# OhEye.net
KiCad netlist of a schematic drawn in EAGLE
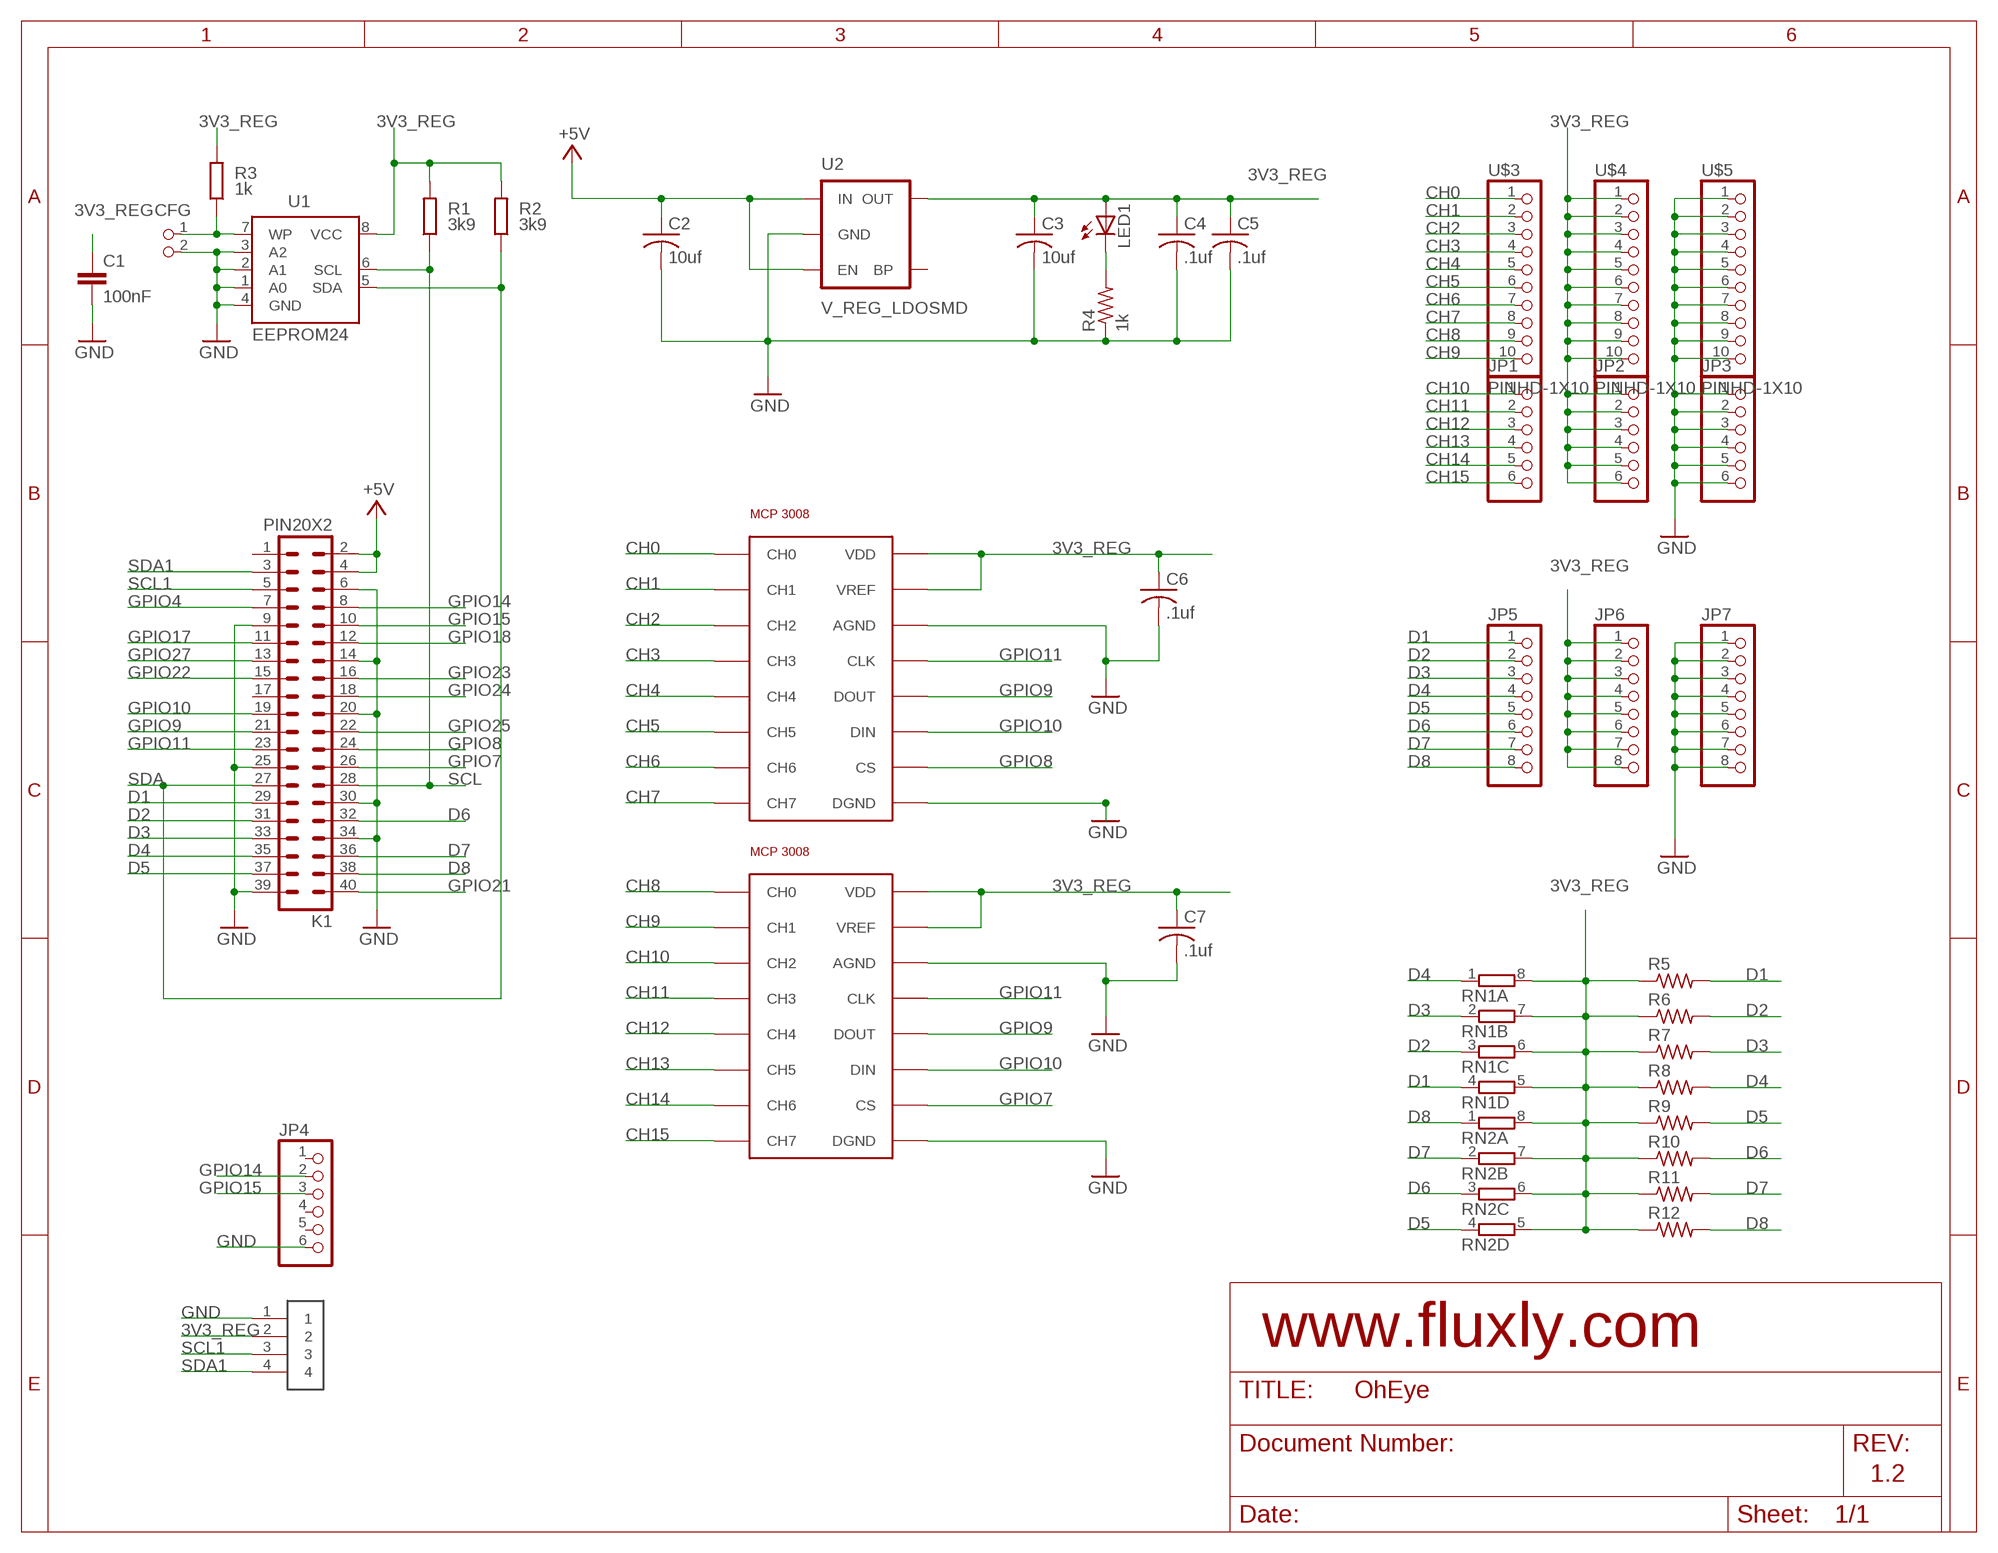
[diagram p0: schematic, sheet 1]

(export (version "E")
  (design (tool "Eeschema 10.0.6"))
  (components
    (comp (ref "C1")
      (value "100nF")
      (footprint "eagle-import:C0805K")
      (libsource (lib "eagle-import") (part "C-EUC0805K"))
    )
    (comp (ref "C2")
      (value "10uf")
      (footprint "eagle-import:C0805K")
      (libsource (lib "eagle-import") (part "C-USC0805K"))
    )
    (comp (ref "C3")
      (value "10uf")
      (footprint "eagle-import:C0805K")
      (libsource (lib "eagle-import") (part "C-USC0805K"))
    )
    (comp (ref "C4")
      (value ".1uf")
      (footprint "eagle-import:C0805K")
      (libsource (lib "eagle-import") (part "C-USC0805K"))
    )
    (comp (ref "C5")
      (value ".1uf")
      (footprint "eagle-import:C0805K")
      (libsource (lib "eagle-import") (part "C-USC0805K"))
    )
    (comp (ref "C6")
      (value ".1uf")
      (footprint "eagle-import:C0805K")
      (libsource (lib "eagle-import") (part "C-USC0805K"))
    )
    (comp (ref "C7")
      (value ".1uf")
      (footprint "eagle-import:C0805K")
      (libsource (lib "eagle-import") (part "C-USC0805K"))
    )
    (comp (ref "CFG")
      (value "PIN2_100")
      (footprint "eagle-import:PIN_W_2")
      (libsource (lib "eagle-import") (part "PIN2_100"))
    )
    (comp (ref "JP1")
      (value "PINHD-1X6B")
      (footprint "eagle-import:1X06-BIG")
      (libsource (lib "eagle-import") (part "PINHD-1X6B"))
    )
    (comp (ref "JP2")
      (value "PINHD-1X6B")
      (footprint "eagle-import:1X06-BIG")
      (libsource (lib "eagle-import") (part "PINHD-1X6B"))
    )
    (comp (ref "JP3")
      (value "PINHD-1X6B")
      (footprint "eagle-import:1X06-BIG")
      (libsource (lib "eagle-import") (part "PINHD-1X6B"))
    )
    (comp (ref "JP4")
      (value "PINHD-1X6B")
      (footprint "eagle-import:1X06-BIG")
      (libsource (lib "eagle-import") (part "PINHD-1X6B"))
    )
    (comp (ref "JP5")
      (value "PINHD-1X8BIG")
      (footprint "eagle-import:1X08-BIG")
      (libsource (lib "eagle-import") (part "PINHD-1X8BIG"))
    )
    (comp (ref "JP6")
      (value "PINHD-1X8BIG")
      (footprint "eagle-import:1X08-BIG")
      (libsource (lib "eagle-import") (part "PINHD-1X8BIG"))
    )
    (comp (ref "JP7")
      (value "PINHD-1X8BIG")
      (footprint "eagle-import:1X08-BIG")
      (libsource (lib "eagle-import") (part "PINHD-1X8BIG"))
    )
    (comp (ref "K1")
      (value "PIN20X2")
      (footprint "eagle-import:PIN_20X2")
      (libsource (lib "eagle-import") (part "PIN20X2"))
    )
    (comp (ref "LED1")
      (value "LEDLED-0805")
      (footprint "eagle-import:LED0805.PAC")
      (libsource (lib "eagle-import") (part "LEDLED-0805"))
    )
    (comp (ref "R1")
      (value "3k9")
      (footprint "eagle-import:M0805")
      (fields (field (name "TOLERANCE") "5%"))
      (libsource (lib "eagle-import") (part "R-EU_M0805"))
    )
    (comp (ref "R2")
      (value "3k9")
      (footprint "eagle-import:M0805")
      (fields (field (name "TOLERANCE") "5%"))
      (libsource (lib "eagle-import") (part "R-EU_M0805"))
    )
    (comp (ref "R3")
      (value "1k")
      (footprint "eagle-import:M0805")
      (fields (field (name "TOLERANCE") "5%"))
      (libsource (lib "eagle-import") (part "R-EU_M0805"))
    )
    (comp (ref "R4")
      (value "1k")
      (footprint "eagle-import:R0805W")
      (libsource (lib "eagle-import") (part "R-US_R0805W"))
    )
    (comp (ref "R5")
      (value "R-US_0207/10")
      (footprint "eagle-import:0207_10")
      (libsource (lib "eagle-import") (part "adafruit_R-US_0207/10"))
    )
    (comp (ref "R6")
      (value "R-US_0207/10")
      (footprint "eagle-import:0207_10")
      (libsource (lib "eagle-import") (part "adafruit_R-US_0207/10"))
    )
    (comp (ref "R7")
      (value "R-US_0207/10")
      (footprint "eagle-import:0207_10")
      (libsource (lib "eagle-import") (part "adafruit_R-US_0207/10"))
    )
    (comp (ref "R8")
      (value "R-US_0207/10")
      (footprint "eagle-import:0207_10")
      (libsource (lib "eagle-import") (part "adafruit_R-US_0207/10"))
    )
    (comp (ref "R9")
      (value "R-US_0207/10")
      (footprint "eagle-import:0207_10")
      (libsource (lib "eagle-import") (part "adafruit_R-US_0207/10"))
    )
    (comp (ref "R10")
      (value "R-US_0207/10")
      (footprint "eagle-import:0207_10")
      (libsource (lib "eagle-import") (part "adafruit_R-US_0207/10"))
    )
    (comp (ref "R11")
      (value "R-US_0207/10")
      (footprint "eagle-import:0207_10")
      (libsource (lib "eagle-import") (part "adafruit_R-US_0207/10"))
    )
    (comp (ref "R12")
      (value "R-US_0207/10")
      (footprint "eagle-import:0207_10")
      (libsource (lib "eagle-import") (part "adafruit_R-US_0207/10"))
    )
    (comp (ref "RN1")
      (value "REISTOR_4NETEXBS8V")
      (footprint "eagle-import:EXBS8V")
      (libsource (lib "eagle-import") (part "REISTOR_4NETEXBS8V"))
    )
    (comp (ref "RN2")
      (value "REISTOR_4NETEXBS8V")
      (footprint "eagle-import:EXBS8V")
      (libsource (lib "eagle-import") (part "REISTOR_4NETEXBS8V"))
    )
    (comp (ref "U$1")
      (value "MCP3008_ADC")
      (footprint "eagle-import:SOIC16")
      (libsource (lib "eagle-import") (part "MCP3008_ADC"))
    )
    (comp (ref "U$2")
      (value "MCP3008_ADC")
      (footprint "eagle-import:SOIC16")
      (libsource (lib "eagle-import") (part "MCP3008_ADC"))
    )
    (comp (ref "U$3")
      (value "PINHD-1X10")
      (footprint "eagle-import:1X10-BIG")
      (libsource (lib "eagle-import") (part "PINHD-1X10"))
    )
    (comp (ref "U$4")
      (value "PINHD-1X10")
      (footprint "eagle-import:1X10-BIG")
      (libsource (lib "eagle-import") (part "PINHD-1X10"))
    )
    (comp (ref "U$5")
      (value "PINHD-1X10")
      (footprint "eagle-import:1X10-BIG")
      (libsource (lib "eagle-import") (part "PINHD-1X10"))
    )
    (comp (ref "U$9")
      (value "1X4_CLEAN")
      (footprint "eagle-import:1X4_CLEAN")
      (libsource (lib "eagle-import") (part "1X4_CLEAN"))
    )
    (comp (ref "U1")
      (value "EEPROM24")
      (footprint "eagle-import:SOIC8")
      (libsource (lib "eagle-import") (part "EEPROM24"))
    )
    (comp (ref "U2")
      (value "V_REG_LDOSMD")
      (footprint "eagle-import:SOT23-5")
      (libsource (lib "eagle-import") (part "V_REG_LDOSMD"))
    )
  )
  (nets
    (net (code "1") (name "+5V") (class "Default")
      (node (ref "C2") (pin "1") (pinfunction "1_1") (pintype "passive"))
      (node (ref "K1") (pin "2") (pinfunction "2_2") (pintype "passive"))
      (node (ref "K1") (pin "4") (pinfunction "4_4") (pintype "passive"))
      (node (ref "U2") (pin "1") (pinfunction "IN_1") (pintype "input"))
      (node (ref "U2") (pin "3") (pinfunction "EN_3") (pintype "input"))
    )
    (net (code "2") (name "/3V3_REG") (class "Default")
      (node (ref "C1") (pin "1") (pinfunction "1_1") (pintype "passive"))
      (node (ref "C3") (pin "1") (pinfunction "1_1") (pintype "passive"))
      (node (ref "C4") (pin "1") (pinfunction "1_1") (pintype "passive"))
      (node (ref "C5") (pin "1") (pinfunction "1_1") (pintype "passive"))
      (node (ref "C6") (pin "1") (pinfunction "1_1") (pintype "passive"))
      (node (ref "C7") (pin "1") (pinfunction "1_1") (pintype "passive"))
      (node (ref "JP2") (pin "1") (pinfunction "1_1") (pintype "passive"))
      (node (ref "JP2") (pin "2") (pinfunction "2_2") (pintype "passive"))
      (node (ref "JP2") (pin "3") (pinfunction "3_3") (pintype "passive"))
      (node (ref "JP2") (pin "4") (pinfunction "4_4") (pintype "passive"))
      (node (ref "JP2") (pin "5") (pinfunction "5_5") (pintype "passive"))
      (node (ref "JP2") (pin "6") (pinfunction "6_6") (pintype "passive"))
      (node (ref "JP6") (pin "1") (pinfunction "1_1") (pintype "passive"))
      (node (ref "JP6") (pin "2") (pinfunction "2_2") (pintype "passive"))
      (node (ref "JP6") (pin "3") (pinfunction "3_3") (pintype "passive"))
      (node (ref "JP6") (pin "4") (pinfunction "4_4") (pintype "passive"))
      (node (ref "JP6") (pin "5") (pinfunction "5_5") (pintype "passive"))
      (node (ref "JP6") (pin "6") (pinfunction "6_6") (pintype "passive"))
      (node (ref "JP6") (pin "7") (pinfunction "7_7") (pintype "passive"))
      (node (ref "JP6") (pin "8") (pinfunction "8_8") (pintype "passive"))
      (node (ref "LED1") (pin "A") (pinfunction "A_A") (pintype "passive"))
      (node (ref "R1") (pin "2") (pinfunction "2_2") (pintype "passive"))
      (node (ref "R10") (pin "1") (pinfunction "1_1") (pintype "passive"))
      (node (ref "R11") (pin "1") (pinfunction "1_1") (pintype "passive"))
      (node (ref "R12") (pin "1") (pinfunction "1_1") (pintype "passive"))
      (node (ref "R2") (pin "2") (pinfunction "2_2") (pintype "passive"))
      (node (ref "R3") (pin "2") (pinfunction "2_2") (pintype "passive"))
      (node (ref "R5") (pin "1") (pinfunction "1_1") (pintype "passive"))
      (node (ref "R6") (pin "1") (pinfunction "1_1") (pintype "passive"))
      (node (ref "R7") (pin "1") (pinfunction "1_1") (pintype "passive"))
      (node (ref "R8") (pin "1") (pinfunction "1_1") (pintype "passive"))
      (node (ref "R9") (pin "1") (pinfunction "1_1") (pintype "passive"))
      (node (ref "RN1") (pin "5") (pinfunction "2_5") (pintype "passive"))
      (node (ref "RN1") (pin "6") (pinfunction "2_6") (pintype "passive"))
      (node (ref "RN1") (pin "7") (pinfunction "2_7") (pintype "passive"))
      (node (ref "RN1") (pin "8") (pinfunction "2_8") (pintype "passive"))
      (node (ref "RN2") (pin "5") (pinfunction "2_5") (pintype "passive"))
      (node (ref "RN2") (pin "6") (pinfunction "2_6") (pintype "passive"))
      (node (ref "RN2") (pin "7") (pinfunction "2_7") (pintype "passive"))
      (node (ref "RN2") (pin "8") (pinfunction "2_8") (pintype "passive"))
      (node (ref "U$1") (pin "P$15") (pinfunction "VREF_P$15") (pintype "bidirectional"))
      (node (ref "U$1") (pin "P$16") (pinfunction "VDD_P$16") (pintype "bidirectional"))
      (node (ref "U$2") (pin "P$15") (pinfunction "VREF_P$15") (pintype "bidirectional"))
      (node (ref "U$2") (pin "P$16") (pinfunction "VDD_P$16") (pintype "bidirectional"))
      (node (ref "U$4") (pin "1") (pinfunction "1_1") (pintype "passive"))
      (node (ref "U$4") (pin "10") (pinfunction "10_10") (pintype "passive"))
      (node (ref "U$4") (pin "2") (pinfunction "2_2") (pintype "passive"))
      (node (ref "U$4") (pin "3") (pinfunction "3_3") (pintype "passive"))
      (node (ref "U$4") (pin "4") (pinfunction "4_4") (pintype "passive"))
      (node (ref "U$4") (pin "5") (pinfunction "5_5") (pintype "passive"))
      (node (ref "U$4") (pin "6") (pinfunction "6_6") (pintype "passive"))
      (node (ref "U$4") (pin "7") (pinfunction "7_7") (pintype "passive"))
      (node (ref "U$4") (pin "8") (pinfunction "8_8") (pintype "passive"))
      (node (ref "U$4") (pin "9") (pinfunction "9_9") (pintype "passive"))
      (node (ref "U$9") (pin "2") (pinfunction "2_2") (pintype "bidirectional"))
      (node (ref "U1") (pin "8") (pinfunction "VCC_8") (pintype "power_in"))
      (node (ref "U2") (pin "5") (pinfunction "OUT_5") (pintype "passive"))
    )
    (net (code "3") (name "/CH0") (class "Default")
      (node (ref "U$1") (pin "P$1") (pinfunction "CH0_P$1") (pintype "bidirectional"))
      (node (ref "U$3") (pin "1") (pinfunction "1_1") (pintype "passive"))
    )
    (net (code "4") (name "/CH1") (class "Default")
      (node (ref "U$1") (pin "P$2") (pinfunction "CH1_P$2") (pintype "bidirectional"))
      (node (ref "U$3") (pin "2") (pinfunction "2_2") (pintype "passive"))
    )
    (net (code "5") (name "/CH2") (class "Default")
      (node (ref "U$1") (pin "P$3") (pinfunction "CH2_P$3") (pintype "bidirectional"))
      (node (ref "U$3") (pin "3") (pinfunction "3_3") (pintype "passive"))
    )
    (net (code "6") (name "/CH3") (class "Default")
      (node (ref "U$1") (pin "P$4") (pinfunction "CH3_P$4") (pintype "bidirectional"))
      (node (ref "U$3") (pin "4") (pinfunction "4_4") (pintype "passive"))
    )
    (net (code "7") (name "/CH4") (class "Default")
      (node (ref "U$1") (pin "P$5") (pinfunction "CH4_P$5") (pintype "bidirectional"))
      (node (ref "U$3") (pin "5") (pinfunction "5_5") (pintype "passive"))
    )
    (net (code "8") (name "/CH5") (class "Default")
      (node (ref "U$1") (pin "P$6") (pinfunction "CH5_P$6") (pintype "bidirectional"))
      (node (ref "U$3") (pin "6") (pinfunction "6_6") (pintype "passive"))
    )
    (net (code "9") (name "/CH6") (class "Default")
      (node (ref "U$1") (pin "P$7") (pinfunction "CH6_P$7") (pintype "bidirectional"))
      (node (ref "U$3") (pin "7") (pinfunction "7_7") (pintype "passive"))
    )
    (net (code "10") (name "/CH7") (class "Default")
      (node (ref "U$1") (pin "P$8") (pinfunction "CH7_P$8") (pintype "bidirectional"))
      (node (ref "U$3") (pin "8") (pinfunction "8_8") (pintype "passive"))
    )
    (net (code "11") (name "/CH8") (class "Default")
      (node (ref "U$2") (pin "P$1") (pinfunction "CH0_P$1") (pintype "bidirectional"))
      (node (ref "U$3") (pin "9") (pinfunction "9_9") (pintype "passive"))
    )
    (net (code "12") (name "/CH9") (class "Default")
      (node (ref "U$2") (pin "P$2") (pinfunction "CH1_P$2") (pintype "bidirectional"))
      (node (ref "U$3") (pin "10") (pinfunction "10_10") (pintype "passive"))
    )
    (net (code "13") (name "/CH10") (class "Default")
      (node (ref "JP1") (pin "1") (pinfunction "1_1") (pintype "passive"))
      (node (ref "U$2") (pin "P$3") (pinfunction "CH2_P$3") (pintype "bidirectional"))
    )
    (net (code "14") (name "/CH11") (class "Default")
      (node (ref "JP1") (pin "2") (pinfunction "2_2") (pintype "passive"))
      (node (ref "U$2") (pin "P$4") (pinfunction "CH3_P$4") (pintype "bidirectional"))
    )
    (net (code "15") (name "/CH12") (class "Default")
      (node (ref "JP1") (pin "3") (pinfunction "3_3") (pintype "passive"))
      (node (ref "U$2") (pin "P$5") (pinfunction "CH4_P$5") (pintype "bidirectional"))
    )
    (net (code "16") (name "/CH13") (class "Default")
      (node (ref "JP1") (pin "4") (pinfunction "4_4") (pintype "passive"))
      (node (ref "U$2") (pin "P$6") (pinfunction "CH5_P$6") (pintype "bidirectional"))
    )
    (net (code "17") (name "/CH14") (class "Default")
      (node (ref "JP1") (pin "5") (pinfunction "5_5") (pintype "passive"))
      (node (ref "U$2") (pin "P$7") (pinfunction "CH6_P$7") (pintype "bidirectional"))
    )
    (net (code "18") (name "/CH15") (class "Default")
      (node (ref "JP1") (pin "6") (pinfunction "6_6") (pintype "passive"))
      (node (ref "U$2") (pin "P$8") (pinfunction "CH7_P$8") (pintype "bidirectional"))
    )
    (net (code "19") (name "/D1") (class "Default")
      (node (ref "JP5") (pin "1") (pinfunction "1_1") (pintype "passive"))
      (node (ref "K1") (pin "29") (pinfunction "29_29") (pintype "passive"))
      (node (ref "R5") (pin "2") (pinfunction "2_2") (pintype "passive"))
      (node (ref "RN1") (pin "4") (pinfunction "1_4") (pintype "passive"))
    )
    (net (code "20") (name "/D2") (class "Default")
      (node (ref "JP5") (pin "2") (pinfunction "2_2") (pintype "passive"))
      (node (ref "K1") (pin "31") (pinfunction "31_31") (pintype "passive"))
      (node (ref "R6") (pin "2") (pinfunction "2_2") (pintype "passive"))
      (node (ref "RN1") (pin "3") (pinfunction "1_3") (pintype "passive"))
    )
    (net (code "21") (name "/D3") (class "Default")
      (node (ref "JP5") (pin "3") (pinfunction "3_3") (pintype "passive"))
      (node (ref "K1") (pin "33") (pinfunction "33_33") (pintype "passive"))
      (node (ref "R7") (pin "2") (pinfunction "2_2") (pintype "passive"))
      (node (ref "RN1") (pin "2") (pinfunction "1_2") (pintype "passive"))
    )
    (net (code "22") (name "/D4") (class "Default")
      (node (ref "JP5") (pin "4") (pinfunction "4_4") (pintype "passive"))
      (node (ref "K1") (pin "35") (pinfunction "35_35") (pintype "passive"))
      (node (ref "R8") (pin "2") (pinfunction "2_2") (pintype "passive"))
      (node (ref "RN1") (pin "1") (pinfunction "1_1") (pintype "passive"))
    )
    (net (code "23") (name "/D5") (class "Default")
      (node (ref "JP5") (pin "5") (pinfunction "5_5") (pintype "passive"))
      (node (ref "K1") (pin "37") (pinfunction "37_37") (pintype "passive"))
      (node (ref "R9") (pin "2") (pinfunction "2_2") (pintype "passive"))
      (node (ref "RN2") (pin "4") (pinfunction "1_4") (pintype "passive"))
    )
    (net (code "24") (name "/D6") (class "Default")
      (node (ref "JP5") (pin "6") (pinfunction "6_6") (pintype "passive"))
      (node (ref "K1") (pin "32") (pinfunction "32_32") (pintype "passive"))
      (node (ref "R10") (pin "2") (pinfunction "2_2") (pintype "passive"))
      (node (ref "RN2") (pin "3") (pinfunction "1_3") (pintype "passive"))
    )
    (net (code "25") (name "/D7") (class "Default")
      (node (ref "JP5") (pin "7") (pinfunction "7_7") (pintype "passive"))
      (node (ref "K1") (pin "36") (pinfunction "36_36") (pintype "passive"))
      (node (ref "R11") (pin "2") (pinfunction "2_2") (pintype "passive"))
      (node (ref "RN2") (pin "2") (pinfunction "1_2") (pintype "passive"))
    )
    (net (code "26") (name "/D8") (class "Default")
      (node (ref "JP5") (pin "8") (pinfunction "8_8") (pintype "passive"))
      (node (ref "K1") (pin "38") (pinfunction "38_38") (pintype "passive"))
      (node (ref "R12") (pin "2") (pinfunction "2_2") (pintype "passive"))
      (node (ref "RN2") (pin "1") (pinfunction "1_1") (pintype "passive"))
    )
    (net (code "27") (name "/GPIO4") (class "Default")
      (node (ref "K1") (pin "7") (pinfunction "7_7") (pintype "passive"))
    )
    (net (code "28") (name "/GPIO7") (class "Default")
      (node (ref "K1") (pin "26") (pinfunction "26_26") (pintype "passive"))
      (node (ref "U$2") (pin "P$10") (pinfunction "CS_P$10") (pintype "bidirectional"))
    )
    (net (code "29") (name "/GPIO8") (class "Default")
      (node (ref "K1") (pin "24") (pinfunction "24_24") (pintype "passive"))
      (node (ref "U$1") (pin "P$10") (pinfunction "CS_P$10") (pintype "bidirectional"))
    )
    (net (code "30") (name "/GPIO9") (class "Default")
      (node (ref "K1") (pin "21") (pinfunction "21_21") (pintype "passive"))
      (node (ref "U$1") (pin "P$12") (pinfunction "DOUT_P$12") (pintype "bidirectional"))
      (node (ref "U$2") (pin "P$12") (pinfunction "DOUT_P$12") (pintype "bidirectional"))
    )
    (net (code "31") (name "/GPIO10") (class "Default")
      (node (ref "K1") (pin "19") (pinfunction "19_19") (pintype "passive"))
      (node (ref "U$1") (pin "P$11") (pinfunction "DIN_P$11") (pintype "bidirectional"))
      (node (ref "U$2") (pin "P$11") (pinfunction "DIN_P$11") (pintype "bidirectional"))
    )
    (net (code "32") (name "/GPIO11") (class "Default")
      (node (ref "K1") (pin "23") (pinfunction "23_23") (pintype "passive"))
      (node (ref "U$1") (pin "P$13") (pinfunction "CLK_P$13") (pintype "bidirectional"))
      (node (ref "U$2") (pin "P$13") (pinfunction "CLK_P$13") (pintype "bidirectional"))
    )
    (net (code "33") (name "/GPIO14") (class "Default")
      (node (ref "JP4") (pin "2") (pinfunction "2_2") (pintype "passive"))
      (node (ref "K1") (pin "8") (pinfunction "8_8") (pintype "passive"))
    )
    (net (code "34") (name "/GPIO15") (class "Default")
      (node (ref "JP4") (pin "3") (pinfunction "3_3") (pintype "passive"))
      (node (ref "K1") (pin "10") (pinfunction "10_10") (pintype "passive"))
    )
    (net (code "35") (name "/GPIO17") (class "Default")
      (node (ref "K1") (pin "11") (pinfunction "11_11") (pintype "passive"))
    )
    (net (code "36") (name "/GPIO18") (class "Default")
      (node (ref "K1") (pin "12") (pinfunction "12_12") (pintype "passive"))
    )
    (net (code "37") (name "/GPIO21") (class "Default")
      (node (ref "K1") (pin "40") (pinfunction "40_40") (pintype "passive"))
    )
    (net (code "38") (name "/GPIO22") (class "Default")
      (node (ref "K1") (pin "15") (pinfunction "15_15") (pintype "passive"))
    )
    (net (code "39") (name "/GPIO23") (class "Default")
      (node (ref "K1") (pin "16") (pinfunction "16_16") (pintype "passive"))
    )
    (net (code "40") (name "/GPIO24") (class "Default")
      (node (ref "K1") (pin "18") (pinfunction "18_18") (pintype "passive"))
    )
    (net (code "41") (name "/GPIO25") (class "Default")
      (node (ref "K1") (pin "22") (pinfunction "22_22") (pintype "passive"))
    )
    (net (code "42") (name "/GPIO27") (class "Default")
      (node (ref "K1") (pin "13") (pinfunction "13_13") (pintype "passive"))
    )
    (net (code "43") (name "/SCL") (class "Default")
      (node (ref "K1") (pin "28") (pinfunction "28_28") (pintype "passive"))
      (node (ref "R1") (pin "1") (pinfunction "1_1") (pintype "passive"))
      (node (ref "U1") (pin "6") (pinfunction "SCL_6") (pintype "input"))
    )
    (net (code "44") (name "/SCL1") (class "Default")
      (node (ref "K1") (pin "5") (pinfunction "5_5") (pintype "passive"))
      (node (ref "U$9") (pin "3") (pinfunction "3_3") (pintype "bidirectional"))
    )
    (net (code "45") (name "/SDA") (class "Default")
      (node (ref "K1") (pin "27") (pinfunction "27_27") (pintype "passive"))
      (node (ref "R2") (pin "1") (pinfunction "1_1") (pintype "passive"))
      (node (ref "U1") (pin "5") (pinfunction "SDA_5") (pintype "bidirectional"))
    )
    (net (code "46") (name "/SDA1") (class "Default")
      (node (ref "K1") (pin "3") (pinfunction "3_3") (pintype "passive"))
      (node (ref "U$9") (pin "4") (pinfunction "4_4") (pintype "bidirectional"))
    )
    (net (code "47") (name "GND") (class "Default")
      (node (ref "C1") (pin "2") (pinfunction "2_2") (pintype "passive"))
      (node (ref "C2") (pin "2") (pinfunction "2_2") (pintype "passive"))
      (node (ref "C3") (pin "2") (pinfunction "2_2") (pintype "passive"))
      (node (ref "C4") (pin "2") (pinfunction "2_2") (pintype "passive"))
      (node (ref "C5") (pin "2") (pinfunction "2_2") (pintype "passive"))
      (node (ref "C6") (pin "2") (pinfunction "2_2") (pintype "passive"))
      (node (ref "C7") (pin "2") (pinfunction "2_2") (pintype "passive"))
      (node (ref "CFG") (pin "2") (pinfunction "2_2") (pintype "passive"))
      (node (ref "JP3") (pin "1") (pinfunction "1_1") (pintype "passive"))
      (node (ref "JP3") (pin "2") (pinfunction "2_2") (pintype "passive"))
      (node (ref "JP3") (pin "3") (pinfunction "3_3") (pintype "passive"))
      (node (ref "JP3") (pin "4") (pinfunction "4_4") (pintype "passive"))
      (node (ref "JP3") (pin "5") (pinfunction "5_5") (pintype "passive"))
      (node (ref "JP3") (pin "6") (pinfunction "6_6") (pintype "passive"))
      (node (ref "JP4") (pin "6") (pinfunction "6_6") (pintype "passive"))
      (node (ref "JP7") (pin "1") (pinfunction "1_1") (pintype "passive"))
      (node (ref "JP7") (pin "2") (pinfunction "2_2") (pintype "passive"))
      (node (ref "JP7") (pin "3") (pinfunction "3_3") (pintype "passive"))
      (node (ref "JP7") (pin "4") (pinfunction "4_4") (pintype "passive"))
      (node (ref "JP7") (pin "5") (pinfunction "5_5") (pintype "passive"))
      (node (ref "JP7") (pin "6") (pinfunction "6_6") (pintype "passive"))
      (node (ref "JP7") (pin "7") (pinfunction "7_7") (pintype "passive"))
      (node (ref "JP7") (pin "8") (pinfunction "8_8") (pintype "passive"))
      (node (ref "K1") (pin "14") (pinfunction "14_14") (pintype "passive"))
      (node (ref "K1") (pin "20") (pinfunction "20_20") (pintype "passive"))
      (node (ref "K1") (pin "25") (pinfunction "25_25") (pintype "passive"))
      (node (ref "K1") (pin "30") (pinfunction "30_30") (pintype "passive"))
      (node (ref "K1") (pin "34") (pinfunction "34_34") (pintype "passive"))
      (node (ref "K1") (pin "39") (pinfunction "39_39") (pintype "passive"))
      (node (ref "K1") (pin "6") (pinfunction "6_6") (pintype "passive"))
      (node (ref "K1") (pin "9") (pinfunction "9_9") (pintype "passive"))
      (node (ref "R4") (pin "1") (pinfunction "1_1") (pintype "passive"))
      (node (ref "U$1") (pin "P$14") (pinfunction "AGND_P$14") (pintype "bidirectional"))
      (node (ref "U$1") (pin "P$9") (pinfunction "DGND_P$9") (pintype "bidirectional"))
      (node (ref "U$2") (pin "P$14") (pinfunction "AGND_P$14") (pintype "bidirectional"))
      (node (ref "U$2") (pin "P$9") (pinfunction "DGND_P$9") (pintype "bidirectional"))
      (node (ref "U$5") (pin "1") (pinfunction "1_1") (pintype "passive"))
      (node (ref "U$5") (pin "10") (pinfunction "10_10") (pintype "passive"))
      (node (ref "U$5") (pin "2") (pinfunction "2_2") (pintype "passive"))
      (node (ref "U$5") (pin "3") (pinfunction "3_3") (pintype "passive"))
      (node (ref "U$5") (pin "4") (pinfunction "4_4") (pintype "passive"))
      (node (ref "U$5") (pin "5") (pinfunction "5_5") (pintype "passive"))
      (node (ref "U$5") (pin "6") (pinfunction "6_6") (pintype "passive"))
      (node (ref "U$5") (pin "7") (pinfunction "7_7") (pintype "passive"))
      (node (ref "U$5") (pin "8") (pinfunction "8_8") (pintype "passive"))
      (node (ref "U$5") (pin "9") (pinfunction "9_9") (pintype "passive"))
      (node (ref "U$9") (pin "1") (pinfunction "1_1") (pintype "bidirectional"))
      (node (ref "U1") (pin "1") (pinfunction "A0_1") (pintype "input"))
      (node (ref "U1") (pin "2") (pinfunction "A1_2") (pintype "input"))
      (node (ref "U1") (pin "3") (pinfunction "A2_3") (pintype "input"))
      (node (ref "U1") (pin "4") (pinfunction "GND_4") (pintype "power_in"))
      (node (ref "U2") (pin "2") (pinfunction "GND_2") (pintype "input"))
    )
    (net (code "48") (name "Net-(LED1-C)") (class "Default")
      (node (ref "LED1") (pin "K") (pinfunction "C_K") (pintype "passive"))
      (node (ref "R4") (pin "2") (pinfunction "2_2") (pintype "passive"))
    )
    (net (code "49") (name "Net-(U1-WP)") (class "Default")
      (node (ref "CFG") (pin "1") (pinfunction "1_1") (pintype "passive"))
      (node (ref "R3") (pin "1") (pinfunction "1_1") (pintype "passive"))
      (node (ref "U1") (pin "7") (pinfunction "WP_7") (pintype "input"))
    )
    (net (code "50") (name "unconnected-(JP4-Pad1)") (class "Default")
      (node (ref "JP4") (pin "1") (pinfunction "1_1") (pintype "passive"))
    )
    (net (code "51") (name "unconnected-(JP4-Pad4)") (class "Default")
      (node (ref "JP4") (pin "4") (pinfunction "4_4") (pintype "passive"))
    )
    (net (code "52") (name "unconnected-(JP4-Pad5)") (class "Default")
      (node (ref "JP4") (pin "5") (pinfunction "5_5") (pintype "passive"))
    )
    (net (code "53") (name "unconnected-(K1-Pad1)") (class "Default")
      (node (ref "K1") (pin "1") (pinfunction "1_1") (pintype "passive"))
    )
    (net (code "54") (name "unconnected-(K1-Pad17)") (class "Default")
      (node (ref "K1") (pin "17") (pinfunction "17_17") (pintype "passive"))
    )
    (net (code "55") (name "unconnected-(U2-BP-Pad4)") (class "Default")
      (node (ref "U2") (pin "4") (pinfunction "BP_4") (pintype "input"))
    )
  )
)
